# Servos.net
KiCad netlist of a schematic drawn in Altium Designer
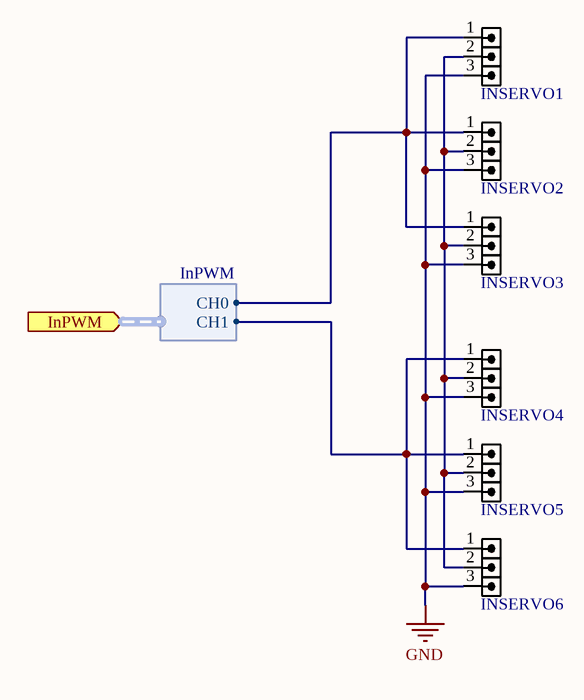
[diagram p0: Servos.SchDoc]

(export (version "E")
  (design (tool "Eeschema 10.0.6"))
  (components
    (comp (ref "INSERVO1")
      (value "HDRM3")
      (footprint "HDR_M_1X3")
      (description "CONN, HEADER, Male, pitch: 2.54mm, 3POS")
      (libsource (lib "Conn Header") (part "HDR_M_1X3"))
    )
    (comp (ref "INSERVO2")
      (value "HDRM3")
      (footprint "HDR_M_1X3")
      (description "CONN, HEADER, Male, pitch: 2.54mm, 3POS")
      (libsource (lib "Conn Header") (part "HDR_M_1X3"))
    )
    (comp (ref "INSERVO3")
      (value "HDRM3")
      (footprint "HDR_M_1X3")
      (description "CONN, HEADER, Male, pitch: 2.54mm, 3POS")
      (libsource (lib "Conn Header") (part "HDR_M_1X3"))
    )
    (comp (ref "INSERVO4")
      (value "HDRM3")
      (footprint "HDR_M_1X3")
      (description "CONN, HEADER, Male, pitch: 2.54mm, 3POS")
      (libsource (lib "Conn Header") (part "HDR_M_1X3"))
    )
    (comp (ref "INSERVO5")
      (value "HDRM3")
      (footprint "HDR_M_1X3")
      (description "CONN, HEADER, Male, pitch: 2.54mm, 3POS")
      (libsource (lib "Conn Header") (part "HDR_M_1X3"))
    )
    (comp (ref "INSERVO6")
      (value "HDRM3")
      (footprint "HDR_M_1X3")
      (description "CONN, HEADER, Male, pitch: 2.54mm, 3POS")
      (libsource (lib "Conn Header") (part "HDR_M_1X3"))
    )
  )
  (nets
    (net (code "3") (name "GND") (class "Default")
      (node (ref "INSERVO1") (pin "3") (pinfunction "3_3") (pintype "passive"))
      (node (ref "INSERVO2") (pin "3") (pinfunction "3_3") (pintype "passive"))
      (node (ref "INSERVO3") (pin "3") (pinfunction "3_3") (pintype "passive"))
      (node (ref "INSERVO4") (pin "3") (pinfunction "3_3") (pintype "passive"))
      (node (ref "INSERVO5") (pin "3") (pinfunction "3_3") (pintype "passive"))
      (node (ref "INSERVO6") (pin "3") (pinfunction "3_3") (pintype "passive"))
    )
    (net (code "4") (name "Net-(INSERVO1-Pad1)") (class "Default")
      (node (ref "INSERVO1") (pin "1") (pinfunction "1_1") (pintype "passive"))
      (node (ref "INSERVO2") (pin "1") (pinfunction "1_1") (pintype "passive"))
      (node (ref "INSERVO3") (pin "1") (pinfunction "1_1") (pintype "passive"))
    )
    (net (code "5") (name "Net-(INSERVO1-Pad2)") (class "Default")
      (node (ref "INSERVO1") (pin "2") (pinfunction "2_2") (pintype "passive"))
      (node (ref "INSERVO2") (pin "2") (pinfunction "2_2") (pintype "passive"))
      (node (ref "INSERVO3") (pin "2") (pinfunction "2_2") (pintype "passive"))
      (node (ref "INSERVO4") (pin "2") (pinfunction "2_2") (pintype "passive"))
      (node (ref "INSERVO5") (pin "2") (pinfunction "2_2") (pintype "passive"))
      (node (ref "INSERVO6") (pin "2") (pinfunction "2_2") (pintype "passive"))
    )
    (net (code "6") (name "Net-(INSERVO4-Pad1)") (class "Default")
      (node (ref "INSERVO4") (pin "1") (pinfunction "1_1") (pintype "passive"))
      (node (ref "INSERVO5") (pin "1") (pinfunction "1_1") (pintype "passive"))
      (node (ref "INSERVO6") (pin "1") (pinfunction "1_1") (pintype "passive"))
    )
  )
)
